# LED_DRIVER.net
KiCad netlist of a schematic drawn in EasyEDA Pro
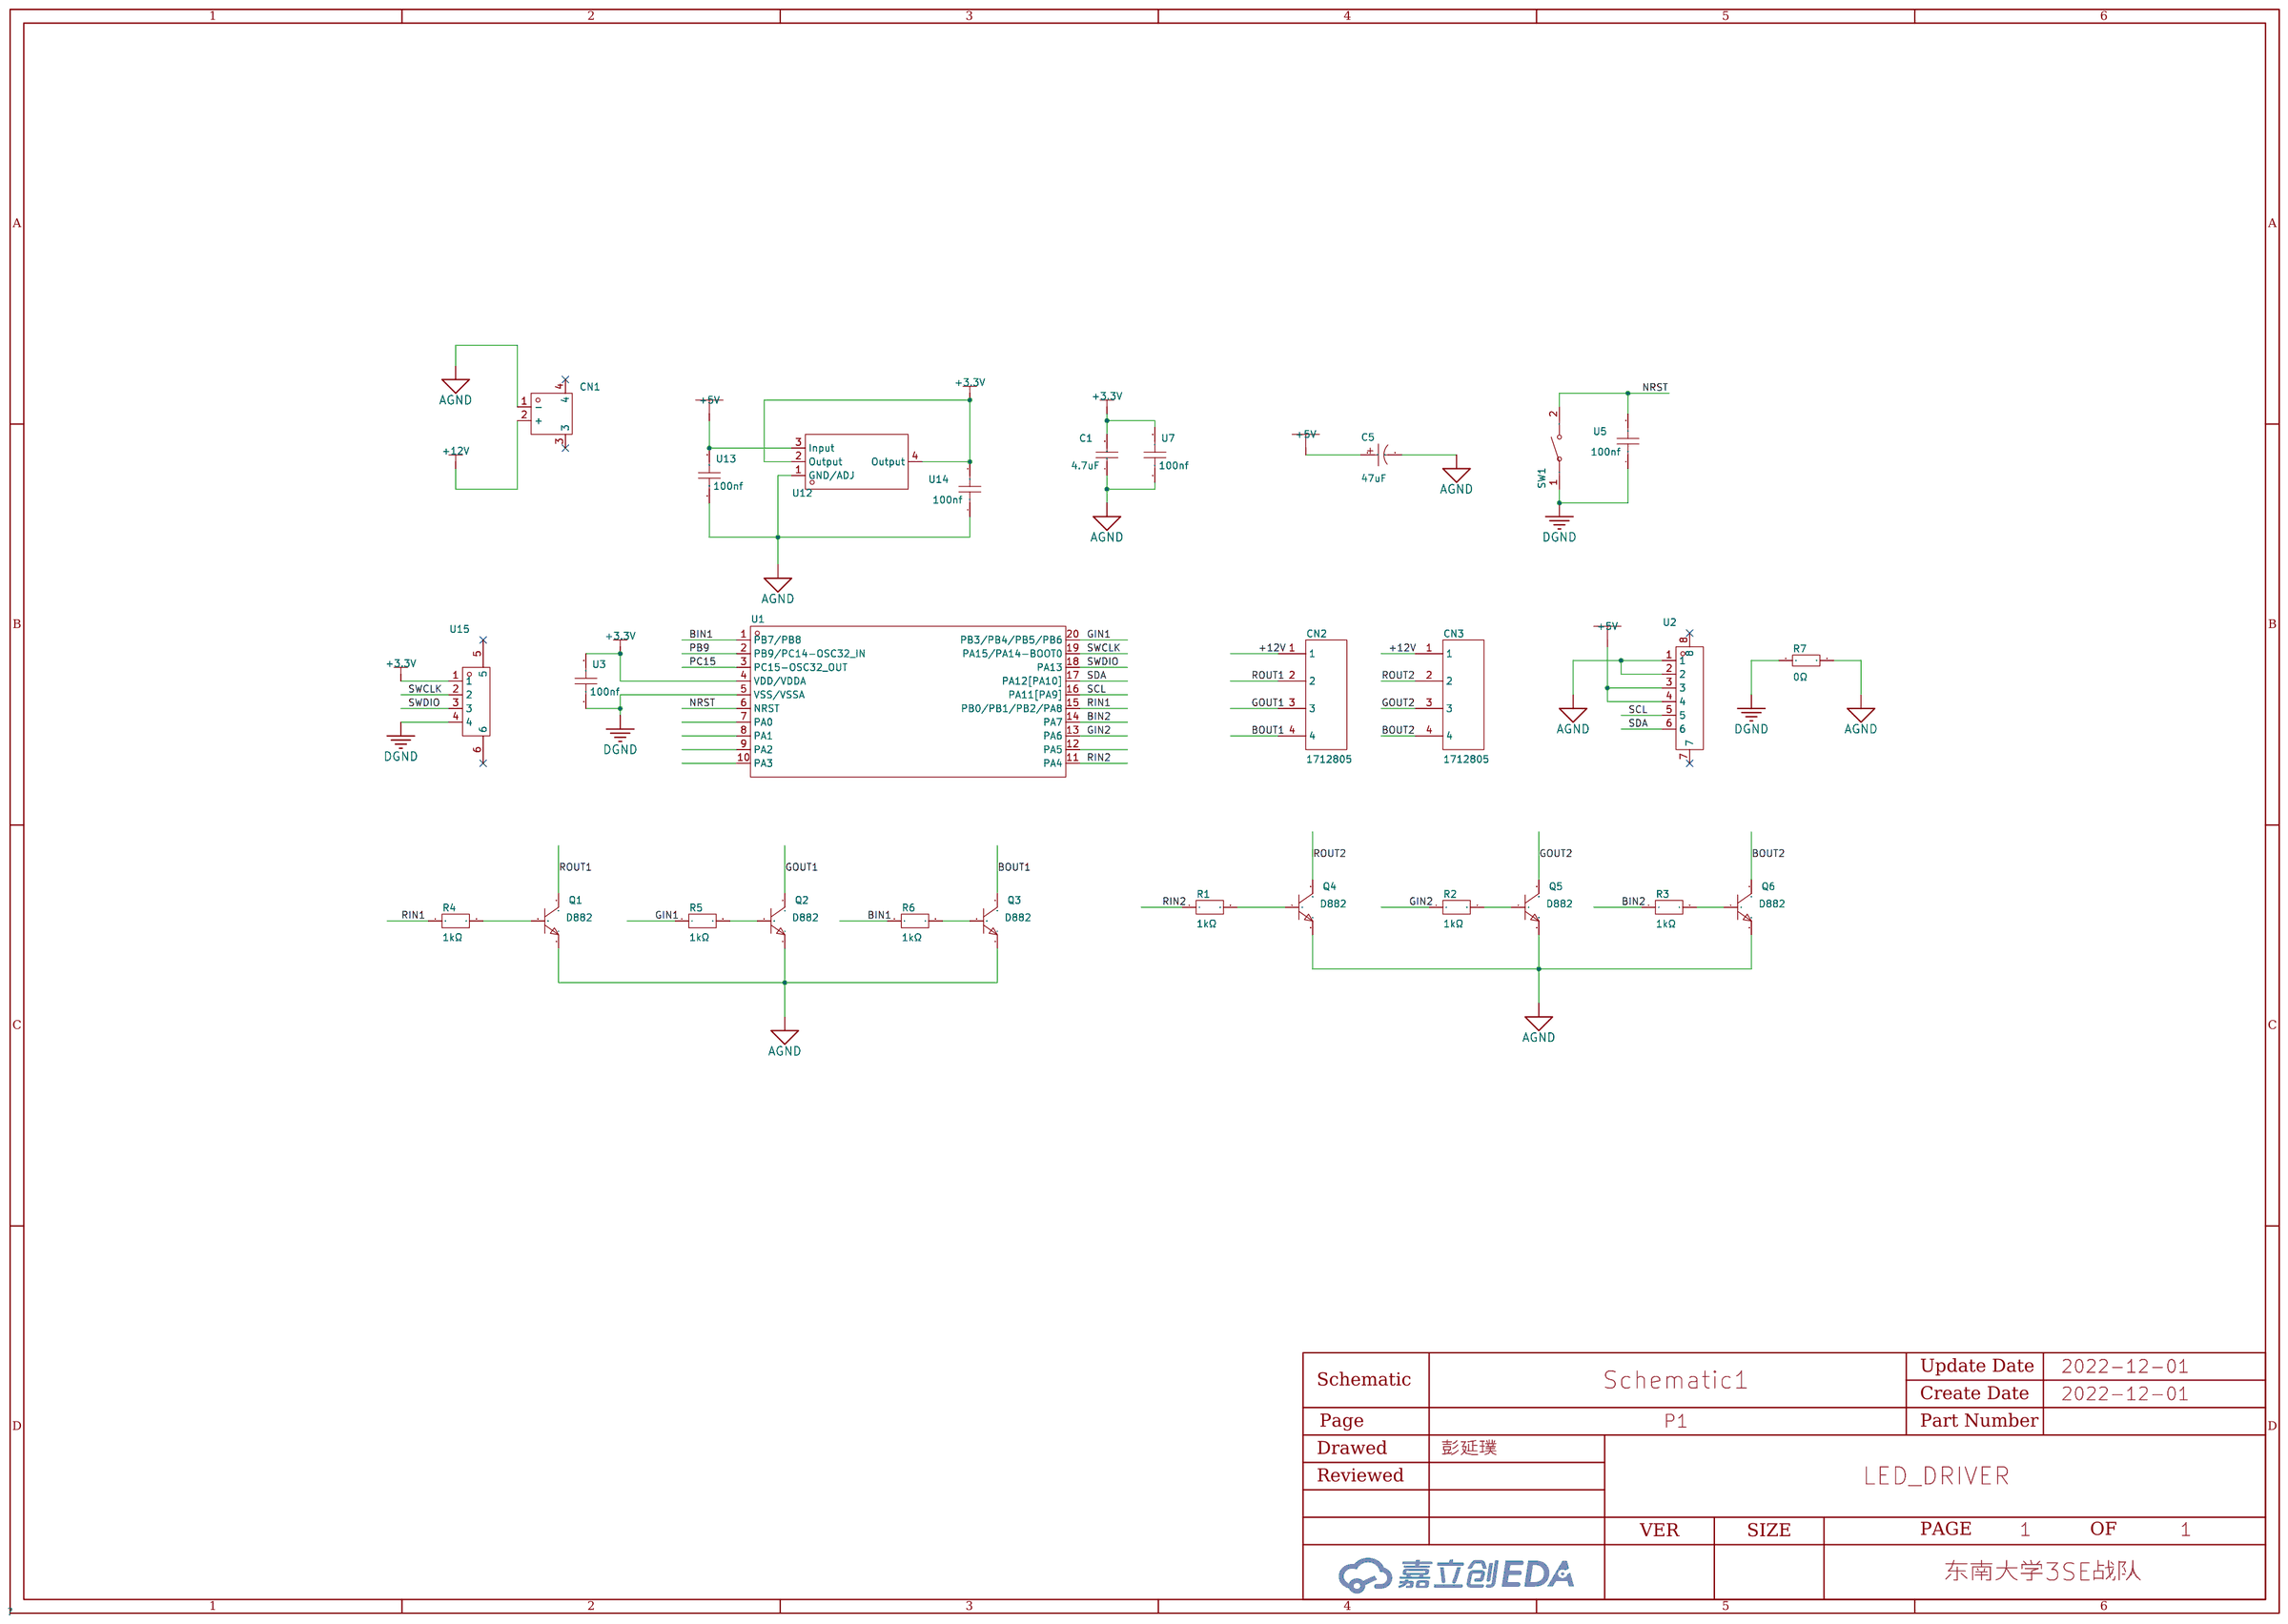
[diagram p0: schematic sheet]

(export (version "E")
  (design (tool "Eeschema 10.0.6"))
  (components
    (comp (ref "C1")
      (value "4.7uF")
      (footprint "easyedapro:C0603")
      (description "容值:4.7uF;精度:±20%;额定电压:16V;温度系数:Y5V;")
      (fields (field (name "Manufacturer Part") "0603F475M160NT") (field (name "Manufacturer") "FH(风华)"))
      (libsource (lib "easyedapro") (part "0603F475M160NT"))
    )
    (comp (ref "C5")
      (value "47uF")
      (footprint "easyedapro:CAP-SMD_BD6.3-L6.6-W6.6-FD")
      (fields (field (name "Manufacturer Part") "RVT1V470M0605") (field (name "Manufacturer") "HONOR(荣誉)"))
      (libsource (lib "easyedapro") (part "RVT1V470M0605"))
    )
    (comp (ref "CN1")
      (value "XT60PW-M")
      (footprint "easyedapro:CONN-TH_XT60PW-M")
      (description "模型锂电连接器")
      (fields (field (name "Manufacturer") "AMASS(艾迈斯)"))
      (libsource (lib "easyedapro") (part "XT60PW-M"))
    )
    (comp (ref "CN2")
      (value "1712805")
      (footprint "easyedapro:CONN-TH_4P-P5.08_1712805")
      (description "间距:5.08mm;排数:1;每排PIN数:4;安装方式:直针;额定电流:24A;额定电压:400V;线规 - AWG:-;线规 - mm?:-;工作温度范围:-;颜色:绿色;")
      (fields (field (name "Manufacturer") "Phoenix Contact(菲尼克斯)"))
      (libsource (lib "easyedapro") (part "MKDS3/4-5.08"))
    )
    (comp (ref "CN3")
      (value "1712805")
      (footprint "easyedapro:CONN-TH_4P-P5.08_1712805")
      (description "间距:5.08mm;排数:1;每排PIN数:4;安装方式:直针;额定电流:24A;额定电压:400V;线规 - AWG:-;线规 - mm?:-;工作温度范围:-;颜色:绿色;")
      (fields (field (name "Manufacturer") "Phoenix Contact(菲尼克斯)"))
      (libsource (lib "easyedapro") (part "MKDS3/4-5.08"))
    )
    (comp (ref "Q1")
      (value "D882")
      (footprint "easyedapro:TO-252-3_L6.5-W5.5-P4.6-LS9.5-BL")
      (fields (field (name "Manufacturer") "YONGYUTAI(永裕泰)"))
      (libsource (lib "easyedapro") (part "D882_C2897489"))
    )
    (comp (ref "Q2")
      (value "D882")
      (footprint "easyedapro:TO-252-3_L6.5-W5.5-P4.6-LS9.5-BL")
      (fields (field (name "Manufacturer") "YONGYUTAI(永裕泰)"))
      (libsource (lib "easyedapro") (part "D882_C2897489"))
    )
    (comp (ref "Q3")
      (value "D882")
      (footprint "easyedapro:TO-252-3_L6.5-W5.5-P4.6-LS9.5-BL")
      (fields (field (name "Manufacturer") "YONGYUTAI(永裕泰)"))
      (libsource (lib "easyedapro") (part "D882_C2897489"))
    )
    (comp (ref "Q4")
      (value "D882")
      (footprint "easyedapro:TO-252-3_L6.5-W5.5-P4.6-LS9.5-BL")
      (fields (field (name "Manufacturer") "YONGYUTAI(永裕泰)"))
      (libsource (lib "easyedapro") (part "D882_C2897489"))
    )
    (comp (ref "Q5")
      (value "D882")
      (footprint "easyedapro:TO-252-3_L6.5-W5.5-P4.6-LS9.5-BL")
      (fields (field (name "Manufacturer") "YONGYUTAI(永裕泰)"))
      (libsource (lib "easyedapro") (part "D882_C2897489"))
    )
    (comp (ref "Q6")
      (value "D882")
      (footprint "easyedapro:TO-252-3_L6.5-W5.5-P4.6-LS9.5-BL")
      (fields (field (name "Manufacturer") "YONGYUTAI(永裕泰)"))
      (libsource (lib "easyedapro") (part "D882_C2897489"))
    )
    (comp (ref "R1")
      (value "1kΩ")
      (footprint "easyedapro:R0603")
      (description "阻值:1kΩ;精度:±5%;")
      (fields (field (name "Manufacturer Part") "SCR0603J1K") (field (name "Manufacturer") "VO(翔胜)"))
      (libsource (lib "easyedapro") (part "SCR0603J1K"))
    )
    (comp (ref "R2")
      (value "1kΩ")
      (footprint "easyedapro:R0603")
      (description "阻值:1kΩ;精度:±5%;")
      (fields (field (name "Manufacturer Part") "SCR0603J1K") (field (name "Manufacturer") "VO(翔胜)"))
      (libsource (lib "easyedapro") (part "SCR0603J1K"))
    )
    (comp (ref "R3")
      (value "1kΩ")
      (footprint "easyedapro:R0603")
      (description "阻值:1kΩ;精度:±5%;")
      (fields (field (name "Manufacturer Part") "SCR0603J1K") (field (name "Manufacturer") "VO(翔胜)"))
      (libsource (lib "easyedapro") (part "SCR0603J1K"))
    )
    (comp (ref "R4")
      (value "1kΩ")
      (footprint "easyedapro:R0603")
      (description "阻值:1kΩ;精度:±5%;")
      (fields (field (name "Manufacturer Part") "SCR0603J1K") (field (name "Manufacturer") "VO(翔胜)"))
      (libsource (lib "easyedapro") (part "SCR0603J1K"))
    )
    (comp (ref "R5")
      (value "1kΩ")
      (footprint "easyedapro:R0603")
      (description "阻值:1kΩ;精度:±5%;")
      (fields (field (name "Manufacturer Part") "SCR0603J1K") (field (name "Manufacturer") "VO(翔胜)"))
      (libsource (lib "easyedapro") (part "SCR0603J1K"))
    )
    (comp (ref "R6")
      (value "1kΩ")
      (footprint "easyedapro:R0603")
      (description "阻值:1kΩ;精度:±5%;")
      (fields (field (name "Manufacturer Part") "SCR0603J1K") (field (name "Manufacturer") "VO(翔胜)"))
      (libsource (lib "easyedapro") (part "SCR0603J1K"))
    )
    (comp (ref "R7")
      (value "0Ω")
      (footprint "easyedapro:R1206")
      (description "阻值:0Ω;精度:-;功率:-;工作温度范围:-55~+155;")
      (fields (field (name "Manufacturer Part") "RK73Z2BTTD") (field (name "Manufacturer") "KOA"))
      (libsource (lib "easyedapro") (part "RK73Z2BTTD"))
    )
    (comp (ref "SW1")
      (value "~")
      (footprint "easyedapro:KEY-SMD_L6.2-W3.6-LS8.0")
      (fields (field (name "Manufacturer Part") "K2-1107ST-A4DW-06") (field (name "Manufacturer") "韩国韩荣"))
      (libsource (lib "easyedapro") (part "K2-1107ST-A4SW-06"))
    )
    (comp (ref "U1")
      (value "STM32G030F6P6")
      (footprint "easyedapro:TSSOP-20_L6.5-W4.4-P0.65-LS6.4-BL")
      (description "CPU位数:-;ROM类型:-;CPU内核:-;主频（MAX):-;工作电压:-;")
      (fields (field (name "Manufacturer") "ST(意法半导体)"))
      (libsource (lib "easyedapro") (part "STM32G030F6P6"))
    )
    (comp (ref "U2")
      (value "~")
      (footprint "easyedapro:CONN-SMD_6P-P1.25_GH1.25-6PWBPZ")
      (fields
        (field (name "Manufacturer Part") "GH1.25-6PWBPZ")
        (field (name "Manufacturer") "BOOMELE(博穆精密)")
      )
      (libsource (lib "easyedapro") (part "GH1.25-6PWBPZ"))
    )
    (comp (ref "U3")
      (value "100nf")
      (footprint "easyedapro:C0603")
      (fields (field (name "Manufacturer Part") "VJ0603Y104KXAAC") (field (name "Manufacturer") "VISHAY(威世)"))
      (libsource (lib "easyedapro") (part "VJ0603Y104KXAAC"))
    )
    (comp (ref "U5")
      (value "100nf")
      (footprint "easyedapro:C0603")
      (fields (field (name "Manufacturer Part") "VJ0603Y104KXAAC") (field (name "Manufacturer") "VISHAY(威世)"))
      (libsource (lib "easyedapro") (part "VJ0603Y104KXAAC"))
    )
    (comp (ref "U7")
      (value "100nf")
      (footprint "easyedapro:C0603")
      (fields (field (name "Manufacturer Part") "VJ0603Y104KXAAC") (field (name "Manufacturer") "VISHAY(威世)"))
      (libsource (lib "easyedapro") (part "VJ0603Y104KXAAC"))
    )
    (comp (ref "U12")
      (value "~")
      (footprint "easyedapro:SOT-223-4_L6.5-W3.5-P2.30-LS7.0-BR")
      (fields (field (name "Manufacturer Part") "AMS1117-3.3") (field (name "Manufacturer") "KEXIN(科信)"))
      (libsource (lib "easyedapro") (part "AMS1117-3.3_C369933"))
    )
    (comp (ref "U13")
      (value "100nf")
      (footprint "easyedapro:C0603")
      (fields (field (name "Manufacturer Part") "VJ0603Y104KXAAC") (field (name "Manufacturer") "VISHAY(威世)"))
      (libsource (lib "easyedapro") (part "VJ0603Y104KXAAC"))
    )
    (comp (ref "U14")
      (value "100nf")
      (footprint "easyedapro:C0603")
      (fields (field (name "Manufacturer Part") "VJ0603Y104KXAAC") (field (name "Manufacturer") "VISHAY(威世)"))
      (libsource (lib "easyedapro") (part "VJ0603Y104KXAAC"))
    )
    (comp (ref "U15")
      (value "~")
      (footprint "easyedapro:CONN-SMD_GH1.25-4PWBPZ")
      (fields
        (field (name "Manufacturer Part") "GH1.25-4PWBPZ")
        (field (name "Manufacturer") "BOOMELE(博穆精密)")
      )
      (libsource (lib "easyedapro") (part "GH1.25-4PWBPZ"))
    )
  )
  (nets
    (net (code "1") (name "+3.3V") (class "Default")
      (node (ref "C1") (pin "2") (pinfunction "2_2") (pintype "input"))
      (node (ref "U1") (pin "4") (pinfunction "VDD/VDDA_4") (pintype "input"))
      (node (ref "U12") (pin "2") (pinfunction "Output_2") (pintype "input"))
      (node (ref "U12") (pin "4") (pinfunction "Output_4") (pintype "input"))
      (node (ref "U14") (pin "2") (pinfunction "2_2") (pintype "input"))
      (node (ref "U15") (pin "1") (pinfunction "1_1") (pintype "input"))
      (node (ref "U3") (pin "2") (pinfunction "2_2") (pintype "input"))
      (node (ref "U7") (pin "2") (pinfunction "2_2") (pintype "input"))
    )
    (net (code "2") (name "+5V") (class "Default")
      (node (ref "C5") (pin "1") (pinfunction "1_1") (pintype "input"))
      (node (ref "U12") (pin "3") (pinfunction "Input_3") (pintype "input"))
      (node (ref "U13") (pin "2") (pinfunction "2_2") (pintype "input"))
      (node (ref "U2") (pin "3") (pinfunction "3_3") (pintype "input"))
      (node (ref "U2") (pin "4") (pinfunction "4_4") (pintype "input"))
    )
    (net (code "3") (name "+12V") (class "Default")
      (node (ref "CN1") (pin "2") (pinfunction "+_2") (pintype "input"))
      (node (ref "CN2") (pin "1") (pinfunction "1_1") (pintype "input"))
      (node (ref "CN3") (pin "1") (pinfunction "1_1") (pintype "input"))
    )
    (net (code "4") (name "/BIN1") (class "Default")
      (node (ref "R6") (pin "1") (pinfunction "1_1") (pintype "input"))
      (node (ref "U1") (pin "1") (pinfunction "PB7/PB8_1") (pintype "input"))
    )
    (net (code "5") (name "/BIN2") (class "Default")
      (node (ref "R3") (pin "1") (pinfunction "1_1") (pintype "input"))
      (node (ref "U1") (pin "14") (pinfunction "PA7_14") (pintype "input"))
    )
    (net (code "6") (name "/BOUT1") (class "Default")
      (node (ref "CN2") (pin "4") (pinfunction "4_4") (pintype "input"))
      (node (ref "Q3") (pin "2") (pinfunction "C_2") (pintype "input"))
    )
    (net (code "7") (name "/BOUT2") (class "Default")
      (node (ref "CN3") (pin "4") (pinfunction "4_4") (pintype "input"))
      (node (ref "Q6") (pin "2") (pinfunction "C_2") (pintype "input"))
    )
    (net (code "8") (name "/GIN1") (class "Default")
      (node (ref "R5") (pin "1") (pinfunction "1_1") (pintype "input"))
      (node (ref "U1") (pin "20") (pinfunction "PB3/PB4/PB5/PB6_20") (pintype "input"))
    )
    (net (code "9") (name "/GIN2") (class "Default")
      (node (ref "R2") (pin "1") (pinfunction "1_1") (pintype "input"))
      (node (ref "U1") (pin "13") (pinfunction "PA6_13") (pintype "input"))
    )
    (net (code "10") (name "/GOUT1") (class "Default")
      (node (ref "CN2") (pin "3") (pinfunction "3_3") (pintype "input"))
      (node (ref "Q2") (pin "2") (pinfunction "C_2") (pintype "input"))
    )
    (net (code "11") (name "/GOUT2") (class "Default")
      (node (ref "CN3") (pin "3") (pinfunction "3_3") (pintype "input"))
      (node (ref "Q5") (pin "2") (pinfunction "C_2") (pintype "input"))
    )
    (net (code "12") (name "/NRST") (class "Default")
      (node (ref "SW1") (pin "2") (pinfunction "2_2") (pintype "input"))
      (node (ref "U1") (pin "6") (pinfunction "NRST_6") (pintype "input"))
      (node (ref "U5") (pin "2") (pinfunction "2_2") (pintype "input"))
    )
    (net (code "13") (name "/PB9") (class "Default")
      (node (ref "U1") (pin "2") (pinfunction "PB9/PC14-OSC32_IN_2") (pintype "input"))
    )
    (net (code "14") (name "/PC15") (class "Default")
      (node (ref "U1") (pin "3") (pinfunction "PC15-OSC32_OUT_3") (pintype "input"))
    )
    (net (code "15") (name "/RIN1") (class "Default")
      (node (ref "R4") (pin "1") (pinfunction "1_1") (pintype "input"))
      (node (ref "U1") (pin "15") (pinfunction "PB0/PB1/PB2/PA8_15") (pintype "input"))
    )
    (net (code "16") (name "/RIN2") (class "Default")
      (node (ref "R1") (pin "1") (pinfunction "1_1") (pintype "input"))
      (node (ref "U1") (pin "11") (pinfunction "PA4_11") (pintype "input"))
    )
    (net (code "17") (name "/ROUT1") (class "Default")
      (node (ref "CN2") (pin "2") (pinfunction "2_2") (pintype "input"))
      (node (ref "Q1") (pin "2") (pinfunction "C_2") (pintype "input"))
    )
    (net (code "18") (name "/ROUT2") (class "Default")
      (node (ref "CN3") (pin "2") (pinfunction "2_2") (pintype "input"))
      (node (ref "Q4") (pin "2") (pinfunction "C_2") (pintype "input"))
    )
    (net (code "19") (name "/SCL") (class "Default")
      (node (ref "U1") (pin "16") (pinfunction "PA11[PA9]_16") (pintype "input"))
      (node (ref "U2") (pin "5") (pinfunction "5_5") (pintype "input"))
    )
    (net (code "20") (name "/SDA") (class "Default")
      (node (ref "U1") (pin "17") (pinfunction "PA12[PA10]_17") (pintype "input"))
      (node (ref "U2") (pin "6") (pinfunction "6_6") (pintype "input"))
    )
    (net (code "21") (name "/SWCLK") (class "Default")
      (node (ref "U1") (pin "19") (pinfunction "PA15/PA14-BOOT0_19") (pintype "input"))
      (node (ref "U15") (pin "2") (pinfunction "2_2") (pintype "input"))
    )
    (net (code "22") (name "/SWDIO") (class "Default")
      (node (ref "U1") (pin "18") (pinfunction "PA13_18") (pintype "input"))
      (node (ref "U15") (pin "3") (pinfunction "3_3") (pintype "input"))
    )
    (net (code "23") (name "AGND") (class "Default")
      (node (ref "C1") (pin "1") (pinfunction "1_1") (pintype "input"))
      (node (ref "C5") (pin "2") (pinfunction "2_2") (pintype "input"))
      (node (ref "CN1") (pin "1") (pinfunction "-_1") (pintype "input"))
      (node (ref "Q1") (pin "3") (pinfunction "E_3") (pintype "input"))
      (node (ref "Q2") (pin "3") (pinfunction "E_3") (pintype "input"))
      (node (ref "Q3") (pin "3") (pinfunction "E_3") (pintype "input"))
      (node (ref "Q4") (pin "3") (pinfunction "E_3") (pintype "input"))
      (node (ref "Q5") (pin "3") (pinfunction "E_3") (pintype "input"))
      (node (ref "Q6") (pin "3") (pinfunction "E_3") (pintype "input"))
      (node (ref "R7") (pin "2") (pinfunction "2_2") (pintype "input"))
      (node (ref "U12") (pin "1") (pinfunction "GND/ADJ_1") (pintype "input"))
      (node (ref "U13") (pin "1") (pinfunction "1_1") (pintype "input"))
      (node (ref "U14") (pin "1") (pinfunction "1_1") (pintype "input"))
      (node (ref "U2") (pin "1") (pinfunction "1_1") (pintype "input"))
      (node (ref "U2") (pin "2") (pinfunction "2_2") (pintype "input"))
      (node (ref "U7") (pin "1") (pinfunction "1_1") (pintype "input"))
    )
    (net (code "24") (name "DGND") (class "Default")
      (node (ref "R7") (pin "1") (pinfunction "1_1") (pintype "input"))
      (node (ref "SW1") (pin "1") (pinfunction "1_1") (pintype "input"))
      (node (ref "U1") (pin "5") (pinfunction "VSS/VSSA_5") (pintype "input"))
      (node (ref "U15") (pin "4") (pinfunction "4_4") (pintype "input"))
      (node (ref "U3") (pin "1") (pinfunction "1_1") (pintype "input"))
      (node (ref "U5") (pin "1") (pinfunction "1_1") (pintype "input"))
    )
    (net (code "25") (name "Net-(Q1-B)") (class "Default")
      (node (ref "Q1") (pin "1") (pinfunction "B_1") (pintype "input"))
      (node (ref "R4") (pin "2") (pinfunction "2_2") (pintype "input"))
    )
    (net (code "26") (name "Net-(Q2-B)") (class "Default")
      (node (ref "Q2") (pin "1") (pinfunction "B_1") (pintype "input"))
      (node (ref "R5") (pin "2") (pinfunction "2_2") (pintype "input"))
    )
    (net (code "27") (name "Net-(Q3-B)") (class "Default")
      (node (ref "Q3") (pin "1") (pinfunction "B_1") (pintype "input"))
      (node (ref "R6") (pin "2") (pinfunction "2_2") (pintype "input"))
    )
    (net (code "28") (name "Net-(Q4-B)") (class "Default")
      (node (ref "Q4") (pin "1") (pinfunction "B_1") (pintype "input"))
      (node (ref "R1") (pin "2") (pinfunction "2_2") (pintype "input"))
    )
    (net (code "29") (name "Net-(Q5-B)") (class "Default")
      (node (ref "Q5") (pin "1") (pinfunction "B_1") (pintype "input"))
      (node (ref "R2") (pin "2") (pinfunction "2_2") (pintype "input"))
    )
    (net (code "30") (name "Net-(Q6-B)") (class "Default")
      (node (ref "Q6") (pin "1") (pinfunction "B_1") (pintype "input"))
      (node (ref "R3") (pin "2") (pinfunction "2_2") (pintype "input"))
    )
    (net (code "31") (name "unconnected-(CN1-Pad3)") (class "Default")
      (node (ref "CN1") (pin "3") (pinfunction "3_3") (pintype "input+no_connect"))
    )
    (net (code "32") (name "unconnected-(CN1-Pad4)") (class "Default")
      (node (ref "CN1") (pin "4") (pinfunction "4_4") (pintype "input+no_connect"))
    )
    (net (code "33") (name "unconnected-(U1-PA0-Pad7)") (class "Default")
      (node (ref "U1") (pin "7") (pinfunction "PA0_7") (pintype "input"))
    )
    (net (code "34") (name "unconnected-(U1-PA1-Pad8)") (class "Default")
      (node (ref "U1") (pin "8") (pinfunction "PA1_8") (pintype "input"))
    )
    (net (code "35") (name "unconnected-(U1-PA2-Pad9)") (class "Default")
      (node (ref "U1") (pin "9") (pinfunction "PA2_9") (pintype "input"))
    )
    (net (code "36") (name "unconnected-(U1-PA3-Pad10)") (class "Default")
      (node (ref "U1") (pin "10") (pinfunction "PA3_10") (pintype "input"))
    )
    (net (code "37") (name "unconnected-(U1-PA5-Pad12)") (class "Default")
      (node (ref "U1") (pin "12") (pinfunction "PA5_12") (pintype "input"))
    )
    (net (code "38") (name "unconnected-(U2-Pad7)") (class "Default")
      (node (ref "U2") (pin "7") (pinfunction "7_7") (pintype "input+no_connect"))
    )
    (net (code "39") (name "unconnected-(U2-Pad8)") (class "Default")
      (node (ref "U2") (pin "8") (pinfunction "8_8") (pintype "input+no_connect"))
    )
    (net (code "40") (name "unconnected-(U15-Pad5)") (class "Default")
      (node (ref "U15") (pin "5") (pinfunction "5_5") (pintype "input+no_connect"))
    )
    (net (code "41") (name "unconnected-(U15-Pad6)") (class "Default")
      (node (ref "U15") (pin "6") (pinfunction "6_6") (pintype "input+no_connect"))
    )
  )
)
